# 5853-base-board.net
KiCad netlist of a schematic drawn in EAGLE
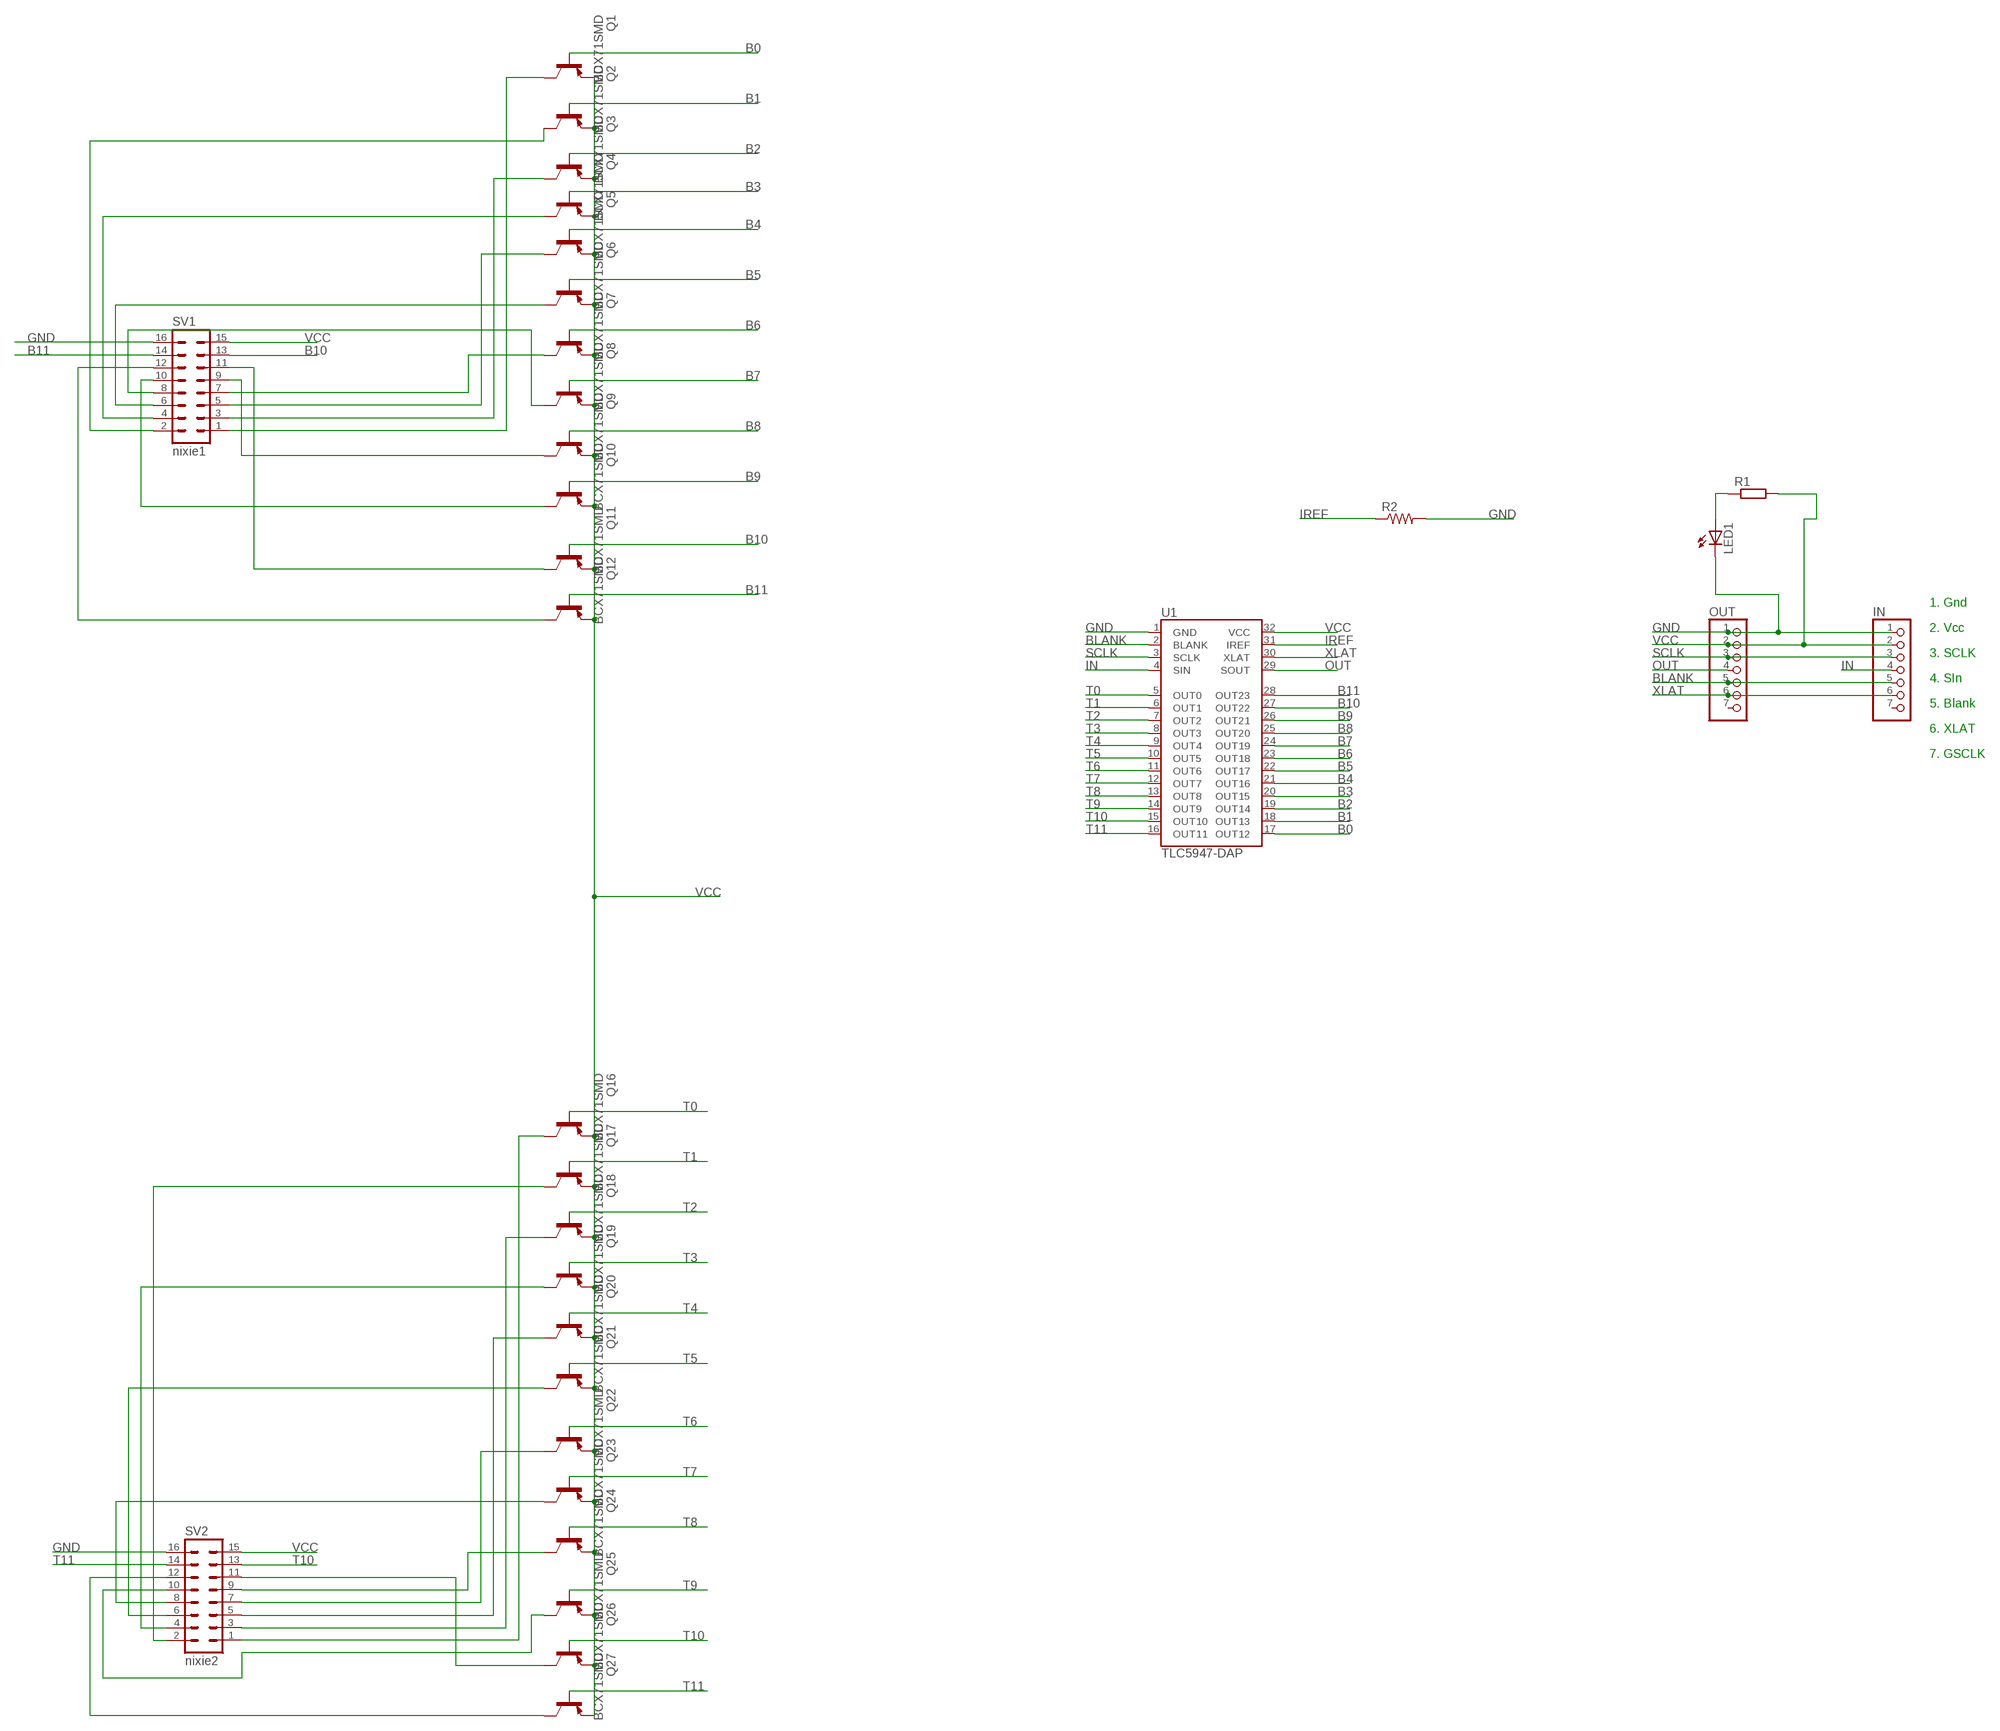
[diagram p0: schematic, sheet 1]

(export (version "E")
  (design (tool "Eeschema 10.0.6"))
  (components
    (comp (ref "IN")
      (value "PINHD-1X7")
      (footprint "eagle-import:1X07")
      (libsource (lib "eagle-import") (part "PINHD-1X7"))
    )
    (comp (ref "LED1")
      (value "LEDCHIPLED_0603")
      (footprint "eagle-import:CHIPLED_0603")
      (libsource (lib "eagle-import") (part "LEDCHIPLED_0603"))
    )
    (comp (ref "OUT")
      (value "PINHD-1X7")
      (footprint "eagle-import:1X07")
      (libsource (lib "eagle-import") (part "PINHD-1X7"))
    )
    (comp (ref "Q1")
      (value "BCX71SMD")
      (footprint "eagle-import:SOT23")
      (libsource (lib "eagle-import") (part "BCX71SMD"))
    )
    (comp (ref "Q2")
      (value "BCX71SMD")
      (footprint "eagle-import:SOT23")
      (libsource (lib "eagle-import") (part "BCX71SMD"))
    )
    (comp (ref "Q3")
      (value "BCX71SMD")
      (footprint "eagle-import:SOT23")
      (libsource (lib "eagle-import") (part "BCX71SMD"))
    )
    (comp (ref "Q4")
      (value "BCX71SMD")
      (footprint "eagle-import:SOT23")
      (libsource (lib "eagle-import") (part "BCX71SMD"))
    )
    (comp (ref "Q5")
      (value "BCX71SMD")
      (footprint "eagle-import:SOT23")
      (libsource (lib "eagle-import") (part "BCX71SMD"))
    )
    (comp (ref "Q6")
      (value "BCX71SMD")
      (footprint "eagle-import:SOT23")
      (libsource (lib "eagle-import") (part "BCX71SMD"))
    )
    (comp (ref "Q7")
      (value "BCX71SMD")
      (footprint "eagle-import:SOT23")
      (libsource (lib "eagle-import") (part "BCX71SMD"))
    )
    (comp (ref "Q8")
      (value "BCX71SMD")
      (footprint "eagle-import:SOT23")
      (libsource (lib "eagle-import") (part "BCX71SMD"))
    )
    (comp (ref "Q9")
      (value "BCX71SMD")
      (footprint "eagle-import:SOT23")
      (libsource (lib "eagle-import") (part "BCX71SMD"))
    )
    (comp (ref "Q10")
      (value "BCX71SMD")
      (footprint "eagle-import:SOT23")
      (libsource (lib "eagle-import") (part "BCX71SMD"))
    )
    (comp (ref "Q11")
      (value "BCX71SMD")
      (footprint "eagle-import:SOT23")
      (libsource (lib "eagle-import") (part "BCX71SMD"))
    )
    (comp (ref "Q12")
      (value "BCX71SMD")
      (footprint "eagle-import:SOT23")
      (libsource (lib "eagle-import") (part "BCX71SMD"))
    )
    (comp (ref "Q16")
      (value "BCX71SMD")
      (footprint "eagle-import:SOT23")
      (libsource (lib "eagle-import") (part "BCX71SMD"))
    )
    (comp (ref "Q17")
      (value "BCX71SMD")
      (footprint "eagle-import:SOT23")
      (libsource (lib "eagle-import") (part "BCX71SMD"))
    )
    (comp (ref "Q18")
      (value "BCX71SMD")
      (footprint "eagle-import:SOT23")
      (libsource (lib "eagle-import") (part "BCX71SMD"))
    )
    (comp (ref "Q19")
      (value "BCX71SMD")
      (footprint "eagle-import:SOT23")
      (libsource (lib "eagle-import") (part "BCX71SMD"))
    )
    (comp (ref "Q20")
      (value "BCX71SMD")
      (footprint "eagle-import:SOT23")
      (libsource (lib "eagle-import") (part "BCX71SMD"))
    )
    (comp (ref "Q21")
      (value "BCX71SMD")
      (footprint "eagle-import:SOT23")
      (libsource (lib "eagle-import") (part "BCX71SMD"))
    )
    (comp (ref "Q22")
      (value "BCX71SMD")
      (footprint "eagle-import:SOT23")
      (libsource (lib "eagle-import") (part "BCX71SMD"))
    )
    (comp (ref "Q23")
      (value "BCX71SMD")
      (footprint "eagle-import:SOT23")
      (libsource (lib "eagle-import") (part "BCX71SMD"))
    )
    (comp (ref "Q24")
      (value "BCX71SMD")
      (footprint "eagle-import:SOT23")
      (libsource (lib "eagle-import") (part "BCX71SMD"))
    )
    (comp (ref "Q25")
      (value "BCX71SMD")
      (footprint "eagle-import:SOT23")
      (libsource (lib "eagle-import") (part "BCX71SMD"))
    )
    (comp (ref "Q26")
      (value "BCX71SMD")
      (footprint "eagle-import:SOT23")
      (libsource (lib "eagle-import") (part "BCX71SMD"))
    )
    (comp (ref "Q27")
      (value "BCX71SMD")
      (footprint "eagle-import:SOT23")
      (libsource (lib "eagle-import") (part "BCX71SMD"))
    )
    (comp (ref "R1")
      (value "R-EU_M0805")
      (footprint "eagle-import:M0805")
      (libsource (lib "eagle-import") (part "R-EU_M0805"))
    )
    (comp (ref "R2")
      (value "R-US_R0805W")
      (footprint "eagle-import:R0805W")
      (libsource (lib "eagle-import") (part "R-US_R0805W"))
    )
    (comp (ref "SV1")
      (value "nixie1")
      (footprint "eagle-import:ML16")
      (libsource (lib "eagle-import") (part "ML16"))
    )
    (comp (ref "SV2")
      (value "nixie2")
      (footprint "eagle-import:ML16")
      (libsource (lib "eagle-import") (part "ML16"))
    )
    (comp (ref "U1")
      (value "TLC5947-DAP")
      (footprint "eagle-import:TSSOP32-GROUNDPAD")
      (libsource (lib "eagle-import") (part "TLC5947-DAP"))
    )
  )
  (nets
    (net (code "1") (name "/B0") (class "Default")
      (node (ref "Q1") (pin "1") (pinfunction "B_1") (pintype "passive"))
      (node (ref "U1") (pin "17") (pinfunction "OUT12_17") (pintype "bidirectional"))
    )
    (net (code "2") (name "/B1") (class "Default")
      (node (ref "Q2") (pin "1") (pinfunction "B_1") (pintype "passive"))
      (node (ref "U1") (pin "18") (pinfunction "OUT13_18") (pintype "bidirectional"))
    )
    (net (code "3") (name "/B2") (class "Default")
      (node (ref "Q3") (pin "1") (pinfunction "B_1") (pintype "passive"))
      (node (ref "U1") (pin "19") (pinfunction "OUT14_19") (pintype "bidirectional"))
    )
    (net (code "4") (name "/B3") (class "Default")
      (node (ref "Q4") (pin "1") (pinfunction "B_1") (pintype "passive"))
      (node (ref "U1") (pin "20") (pinfunction "OUT15_20") (pintype "bidirectional"))
    )
    (net (code "5") (name "/B4") (class "Default")
      (node (ref "Q5") (pin "1") (pinfunction "B_1") (pintype "passive"))
      (node (ref "U1") (pin "21") (pinfunction "OUT16_21") (pintype "bidirectional"))
    )
    (net (code "6") (name "/B5") (class "Default")
      (node (ref "Q6") (pin "1") (pinfunction "B_1") (pintype "passive"))
      (node (ref "U1") (pin "22") (pinfunction "OUT17_22") (pintype "bidirectional"))
    )
    (net (code "7") (name "/B6") (class "Default")
      (node (ref "Q7") (pin "1") (pinfunction "B_1") (pintype "passive"))
      (node (ref "U1") (pin "23") (pinfunction "OUT18_23") (pintype "bidirectional"))
    )
    (net (code "8") (name "/B7") (class "Default")
      (node (ref "Q8") (pin "1") (pinfunction "B_1") (pintype "passive"))
      (node (ref "U1") (pin "24") (pinfunction "OUT19_24") (pintype "bidirectional"))
    )
    (net (code "9") (name "/B8") (class "Default")
      (node (ref "Q9") (pin "1") (pinfunction "B_1") (pintype "passive"))
      (node (ref "U1") (pin "25") (pinfunction "OUT20_25") (pintype "bidirectional"))
    )
    (net (code "10") (name "/B9") (class "Default")
      (node (ref "Q10") (pin "1") (pinfunction "B_1") (pintype "passive"))
      (node (ref "U1") (pin "26") (pinfunction "OUT21_26") (pintype "bidirectional"))
    )
    (net (code "11") (name "/B10") (class "Default")
      (node (ref "Q11") (pin "1") (pinfunction "B_1") (pintype "passive"))
      (node (ref "SV1") (pin "13") (pinfunction "13_13") (pintype "passive"))
      (node (ref "U1") (pin "27") (pinfunction "OUT22_27") (pintype "bidirectional"))
    )
    (net (code "12") (name "/B11") (class "Default")
      (node (ref "Q12") (pin "1") (pinfunction "B_1") (pintype "passive"))
      (node (ref "SV1") (pin "14") (pinfunction "14_14") (pintype "passive"))
      (node (ref "U1") (pin "28") (pinfunction "OUT23_28") (pintype "bidirectional"))
    )
    (net (code "13") (name "/BLANK") (class "Default")
      (node (ref "IN") (pin "5") (pinfunction "5_5") (pintype "passive"))
      (node (ref "OUT") (pin "5") (pinfunction "5_5") (pintype "passive"))
      (node (ref "U1") (pin "2") (pinfunction "BLANK_2") (pintype "bidirectional"))
    )
    (net (code "14") (name "/GND") (class "Default")
      (node (ref "IN") (pin "1") (pinfunction "1_1") (pintype "passive"))
      (node (ref "LED1") (pin "C") (pinfunction "C_C") (pintype "passive"))
      (node (ref "OUT") (pin "1") (pinfunction "1_1") (pintype "passive"))
      (node (ref "R2") (pin "2") (pinfunction "2_2") (pintype "passive"))
      (node (ref "SV1") (pin "16") (pinfunction "16_16") (pintype "passive"))
      (node (ref "SV2") (pin "16") (pinfunction "16_16") (pintype "passive"))
      (node (ref "U1") (pin "1") (pinfunction "GND_1") (pintype "bidirectional"))
    )
    (net (code "15") (name "/IN") (class "Default")
      (node (ref "IN") (pin "4") (pinfunction "4_4") (pintype "passive"))
      (node (ref "U1") (pin "4") (pinfunction "SIN_4") (pintype "bidirectional"))
    )
    (net (code "16") (name "/IREF") (class "Default")
      (node (ref "R2") (pin "1") (pinfunction "1_1") (pintype "passive"))
      (node (ref "U1") (pin "31") (pinfunction "IREF_31") (pintype "bidirectional"))
    )
    (net (code "17") (name "/OUT") (class "Default")
      (node (ref "OUT") (pin "4") (pinfunction "4_4") (pintype "passive"))
      (node (ref "U1") (pin "29") (pinfunction "SOUT_29") (pintype "bidirectional"))
    )
    (net (code "18") (name "/SCLK") (class "Default")
      (node (ref "IN") (pin "3") (pinfunction "3_3") (pintype "passive"))
      (node (ref "OUT") (pin "3") (pinfunction "3_3") (pintype "passive"))
      (node (ref "U1") (pin "3") (pinfunction "SCLK_3") (pintype "bidirectional"))
    )
    (net (code "19") (name "/T0") (class "Default")
      (node (ref "Q16") (pin "1") (pinfunction "B_1") (pintype "passive"))
      (node (ref "U1") (pin "5") (pinfunction "OUT0_5") (pintype "bidirectional"))
    )
    (net (code "20") (name "/T1") (class "Default")
      (node (ref "Q17") (pin "1") (pinfunction "B_1") (pintype "passive"))
      (node (ref "U1") (pin "6") (pinfunction "OUT1_6") (pintype "bidirectional"))
    )
    (net (code "21") (name "/T2") (class "Default")
      (node (ref "Q18") (pin "1") (pinfunction "B_1") (pintype "passive"))
      (node (ref "U1") (pin "7") (pinfunction "OUT2_7") (pintype "bidirectional"))
    )
    (net (code "22") (name "/T3") (class "Default")
      (node (ref "Q19") (pin "1") (pinfunction "B_1") (pintype "passive"))
      (node (ref "U1") (pin "8") (pinfunction "OUT3_8") (pintype "bidirectional"))
    )
    (net (code "23") (name "/T4") (class "Default")
      (node (ref "Q20") (pin "1") (pinfunction "B_1") (pintype "passive"))
      (node (ref "U1") (pin "9") (pinfunction "OUT4_9") (pintype "bidirectional"))
    )
    (net (code "24") (name "/T5") (class "Default")
      (node (ref "Q21") (pin "1") (pinfunction "B_1") (pintype "passive"))
      (node (ref "U1") (pin "10") (pinfunction "OUT5_10") (pintype "bidirectional"))
    )
    (net (code "25") (name "/T6") (class "Default")
      (node (ref "Q22") (pin "1") (pinfunction "B_1") (pintype "passive"))
      (node (ref "U1") (pin "11") (pinfunction "OUT6_11") (pintype "bidirectional"))
    )
    (net (code "26") (name "/T7") (class "Default")
      (node (ref "Q23") (pin "1") (pinfunction "B_1") (pintype "passive"))
      (node (ref "U1") (pin "12") (pinfunction "OUT7_12") (pintype "bidirectional"))
    )
    (net (code "27") (name "/T8") (class "Default")
      (node (ref "Q24") (pin "1") (pinfunction "B_1") (pintype "passive"))
      (node (ref "U1") (pin "13") (pinfunction "OUT8_13") (pintype "bidirectional"))
    )
    (net (code "28") (name "/T9") (class "Default")
      (node (ref "Q25") (pin "1") (pinfunction "B_1") (pintype "passive"))
      (node (ref "U1") (pin "14") (pinfunction "OUT9_14") (pintype "bidirectional"))
    )
    (net (code "29") (name "/T10") (class "Default")
      (node (ref "Q26") (pin "1") (pinfunction "B_1") (pintype "passive"))
      (node (ref "SV2") (pin "13") (pinfunction "13_13") (pintype "passive"))
      (node (ref "U1") (pin "15") (pinfunction "OUT10_15") (pintype "bidirectional"))
    )
    (net (code "30") (name "/T11") (class "Default")
      (node (ref "Q27") (pin "1") (pinfunction "B_1") (pintype "passive"))
      (node (ref "SV2") (pin "14") (pinfunction "14_14") (pintype "passive"))
      (node (ref "U1") (pin "16") (pinfunction "OUT11_16") (pintype "bidirectional"))
    )
    (net (code "31") (name "/VCC") (class "Default")
      (node (ref "IN") (pin "2") (pinfunction "2_2") (pintype "passive"))
      (node (ref "OUT") (pin "2") (pinfunction "2_2") (pintype "passive"))
      (node (ref "Q1") (pin "2") (pinfunction "E_2") (pintype "passive"))
      (node (ref "Q10") (pin "2") (pinfunction "E_2") (pintype "passive"))
      (node (ref "Q11") (pin "2") (pinfunction "E_2") (pintype "passive"))
      (node (ref "Q12") (pin "2") (pinfunction "E_2") (pintype "passive"))
      (node (ref "Q16") (pin "2") (pinfunction "E_2") (pintype "passive"))
      (node (ref "Q17") (pin "2") (pinfunction "E_2") (pintype "passive"))
      (node (ref "Q18") (pin "2") (pinfunction "E_2") (pintype "passive"))
      (node (ref "Q19") (pin "2") (pinfunction "E_2") (pintype "passive"))
      (node (ref "Q2") (pin "2") (pinfunction "E_2") (pintype "passive"))
      (node (ref "Q20") (pin "2") (pinfunction "E_2") (pintype "passive"))
      (node (ref "Q21") (pin "2") (pinfunction "E_2") (pintype "passive"))
      (node (ref "Q22") (pin "2") (pinfunction "E_2") (pintype "passive"))
      (node (ref "Q23") (pin "2") (pinfunction "E_2") (pintype "passive"))
      (node (ref "Q24") (pin "2") (pinfunction "E_2") (pintype "passive"))
      (node (ref "Q25") (pin "2") (pinfunction "E_2") (pintype "passive"))
      (node (ref "Q26") (pin "2") (pinfunction "E_2") (pintype "passive"))
      (node (ref "Q27") (pin "2") (pinfunction "E_2") (pintype "passive"))
      (node (ref "Q3") (pin "2") (pinfunction "E_2") (pintype "passive"))
      (node (ref "Q4") (pin "2") (pinfunction "E_2") (pintype "passive"))
      (node (ref "Q5") (pin "2") (pinfunction "E_2") (pintype "passive"))
      (node (ref "Q6") (pin "2") (pinfunction "E_2") (pintype "passive"))
      (node (ref "Q7") (pin "2") (pinfunction "E_2") (pintype "passive"))
      (node (ref "Q8") (pin "2") (pinfunction "E_2") (pintype "passive"))
      (node (ref "Q9") (pin "2") (pinfunction "E_2") (pintype "passive"))
      (node (ref "R1") (pin "2") (pinfunction "2_2") (pintype "passive"))
      (node (ref "SV1") (pin "15") (pinfunction "15_15") (pintype "passive"))
      (node (ref "SV2") (pin "15") (pinfunction "15_15") (pintype "passive"))
      (node (ref "U1") (pin "32") (pinfunction "VCC_32") (pintype "bidirectional"))
    )
    (net (code "32") (name "/XLAT") (class "Default")
      (node (ref "IN") (pin "6") (pinfunction "6_6") (pintype "passive"))
      (node (ref "OUT") (pin "6") (pinfunction "6_6") (pintype "passive"))
      (node (ref "U1") (pin "30") (pinfunction "XLAT_30") (pintype "bidirectional"))
    )
    (net (code "33") (name "Net-(LED1-PadA)") (class "Default")
      (node (ref "LED1") (pin "A") (pinfunction "A_A") (pintype "passive"))
      (node (ref "R1") (pin "1") (pinfunction "1_1") (pintype "passive"))
    )
    (net (code "34") (name "Net-(Q1-C)") (class "Default")
      (node (ref "Q1") (pin "3") (pinfunction "C_3") (pintype "passive"))
      (node (ref "SV1") (pin "1") (pinfunction "1_1") (pintype "passive"))
    )
    (net (code "35") (name "Net-(Q2-C)") (class "Default")
      (node (ref "Q2") (pin "3") (pinfunction "C_3") (pintype "passive"))
      (node (ref "SV1") (pin "2") (pinfunction "2_2") (pintype "passive"))
    )
    (net (code "36") (name "Net-(Q3-C)") (class "Default")
      (node (ref "Q3") (pin "3") (pinfunction "C_3") (pintype "passive"))
      (node (ref "SV1") (pin "3") (pinfunction "3_3") (pintype "passive"))
    )
    (net (code "37") (name "Net-(Q4-C)") (class "Default")
      (node (ref "Q4") (pin "3") (pinfunction "C_3") (pintype "passive"))
      (node (ref "SV1") (pin "4") (pinfunction "4_4") (pintype "passive"))
    )
    (net (code "38") (name "Net-(Q5-C)") (class "Default")
      (node (ref "Q5") (pin "3") (pinfunction "C_3") (pintype "passive"))
      (node (ref "SV1") (pin "5") (pinfunction "5_5") (pintype "passive"))
    )
    (net (code "39") (name "Net-(Q6-C)") (class "Default")
      (node (ref "Q6") (pin "3") (pinfunction "C_3") (pintype "passive"))
      (node (ref "SV1") (pin "6") (pinfunction "6_6") (pintype "passive"))
    )
    (net (code "40") (name "Net-(Q7-C)") (class "Default")
      (node (ref "Q7") (pin "3") (pinfunction "C_3") (pintype "passive"))
      (node (ref "SV1") (pin "7") (pinfunction "7_7") (pintype "passive"))
    )
    (net (code "41") (name "Net-(Q8-C)") (class "Default")
      (node (ref "Q8") (pin "3") (pinfunction "C_3") (pintype "passive"))
      (node (ref "SV1") (pin "8") (pinfunction "8_8") (pintype "passive"))
    )
    (net (code "42") (name "Net-(Q9-C)") (class "Default")
      (node (ref "Q9") (pin "3") (pinfunction "C_3") (pintype "passive"))
      (node (ref "SV1") (pin "9") (pinfunction "9_9") (pintype "passive"))
    )
    (net (code "43") (name "Net-(Q10-C)") (class "Default")
      (node (ref "Q10") (pin "3") (pinfunction "C_3") (pintype "passive"))
      (node (ref "SV1") (pin "10") (pinfunction "10_10") (pintype "passive"))
    )
    (net (code "44") (name "Net-(Q11-C)") (class "Default")
      (node (ref "Q11") (pin "3") (pinfunction "C_3") (pintype "passive"))
      (node (ref "SV1") (pin "11") (pinfunction "11_11") (pintype "passive"))
    )
    (net (code "45") (name "Net-(Q12-C)") (class "Default")
      (node (ref "Q12") (pin "3") (pinfunction "C_3") (pintype "passive"))
      (node (ref "SV1") (pin "12") (pinfunction "12_12") (pintype "passive"))
    )
    (net (code "46") (name "Net-(Q16-C)") (class "Default")
      (node (ref "Q16") (pin "3") (pinfunction "C_3") (pintype "passive"))
      (node (ref "SV2") (pin "1") (pinfunction "1_1") (pintype "passive"))
    )
    (net (code "47") (name "Net-(Q17-C)") (class "Default")
      (node (ref "Q17") (pin "3") (pinfunction "C_3") (pintype "passive"))
      (node (ref "SV2") (pin "2") (pinfunction "2_2") (pintype "passive"))
    )
    (net (code "48") (name "Net-(Q18-C)") (class "Default")
      (node (ref "Q18") (pin "3") (pinfunction "C_3") (pintype "passive"))
      (node (ref "SV2") (pin "3") (pinfunction "3_3") (pintype "passive"))
    )
    (net (code "49") (name "Net-(Q19-C)") (class "Default")
      (node (ref "Q19") (pin "3") (pinfunction "C_3") (pintype "passive"))
      (node (ref "SV2") (pin "4") (pinfunction "4_4") (pintype "passive"))
    )
    (net (code "50") (name "Net-(Q20-C)") (class "Default")
      (node (ref "Q20") (pin "3") (pinfunction "C_3") (pintype "passive"))
      (node (ref "SV2") (pin "5") (pinfunction "5_5") (pintype "passive"))
    )
    (net (code "51") (name "Net-(Q21-C)") (class "Default")
      (node (ref "Q21") (pin "3") (pinfunction "C_3") (pintype "passive"))
      (node (ref "SV2") (pin "6") (pinfunction "6_6") (pintype "passive"))
    )
    (net (code "52") (name "Net-(Q22-C)") (class "Default")
      (node (ref "Q22") (pin "3") (pinfunction "C_3") (pintype "passive"))
      (node (ref "SV2") (pin "7") (pinfunction "7_7") (pintype "passive"))
    )
    (net (code "53") (name "Net-(Q23-C)") (class "Default")
      (node (ref "Q23") (pin "3") (pinfunction "C_3") (pintype "passive"))
      (node (ref "SV2") (pin "8") (pinfunction "8_8") (pintype "passive"))
    )
    (net (code "54") (name "Net-(Q24-C)") (class "Default")
      (node (ref "Q24") (pin "3") (pinfunction "C_3") (pintype "passive"))
      (node (ref "SV2") (pin "9") (pinfunction "9_9") (pintype "passive"))
    )
    (net (code "55") (name "Net-(Q25-C)") (class "Default")
      (node (ref "Q25") (pin "3") (pinfunction "C_3") (pintype "passive"))
      (node (ref "SV2") (pin "10") (pinfunction "10_10") (pintype "passive"))
    )
    (net (code "56") (name "Net-(Q26-C)") (class "Default")
      (node (ref "Q26") (pin "3") (pinfunction "C_3") (pintype "passive"))
      (node (ref "SV2") (pin "11") (pinfunction "11_11") (pintype "passive"))
    )
    (net (code "57") (name "Net-(Q27-C)") (class "Default")
      (node (ref "Q27") (pin "3") (pinfunction "C_3") (pintype "passive"))
      (node (ref "SV2") (pin "12") (pinfunction "12_12") (pintype "passive"))
    )
    (net (code "58") (name "unconnected-(IN-Pad7)") (class "Default")
      (node (ref "IN") (pin "7") (pinfunction "7_7") (pintype "passive"))
    )
    (net (code "59") (name "unconnected-(OUT-Pad7)") (class "Default")
      (node (ref "OUT") (pin "7") (pinfunction "7_7") (pintype "passive"))
    )
  )
)
